# wagband_schematic_pre_route.net
KiCad netlist of a schematic drawn in EAGLE
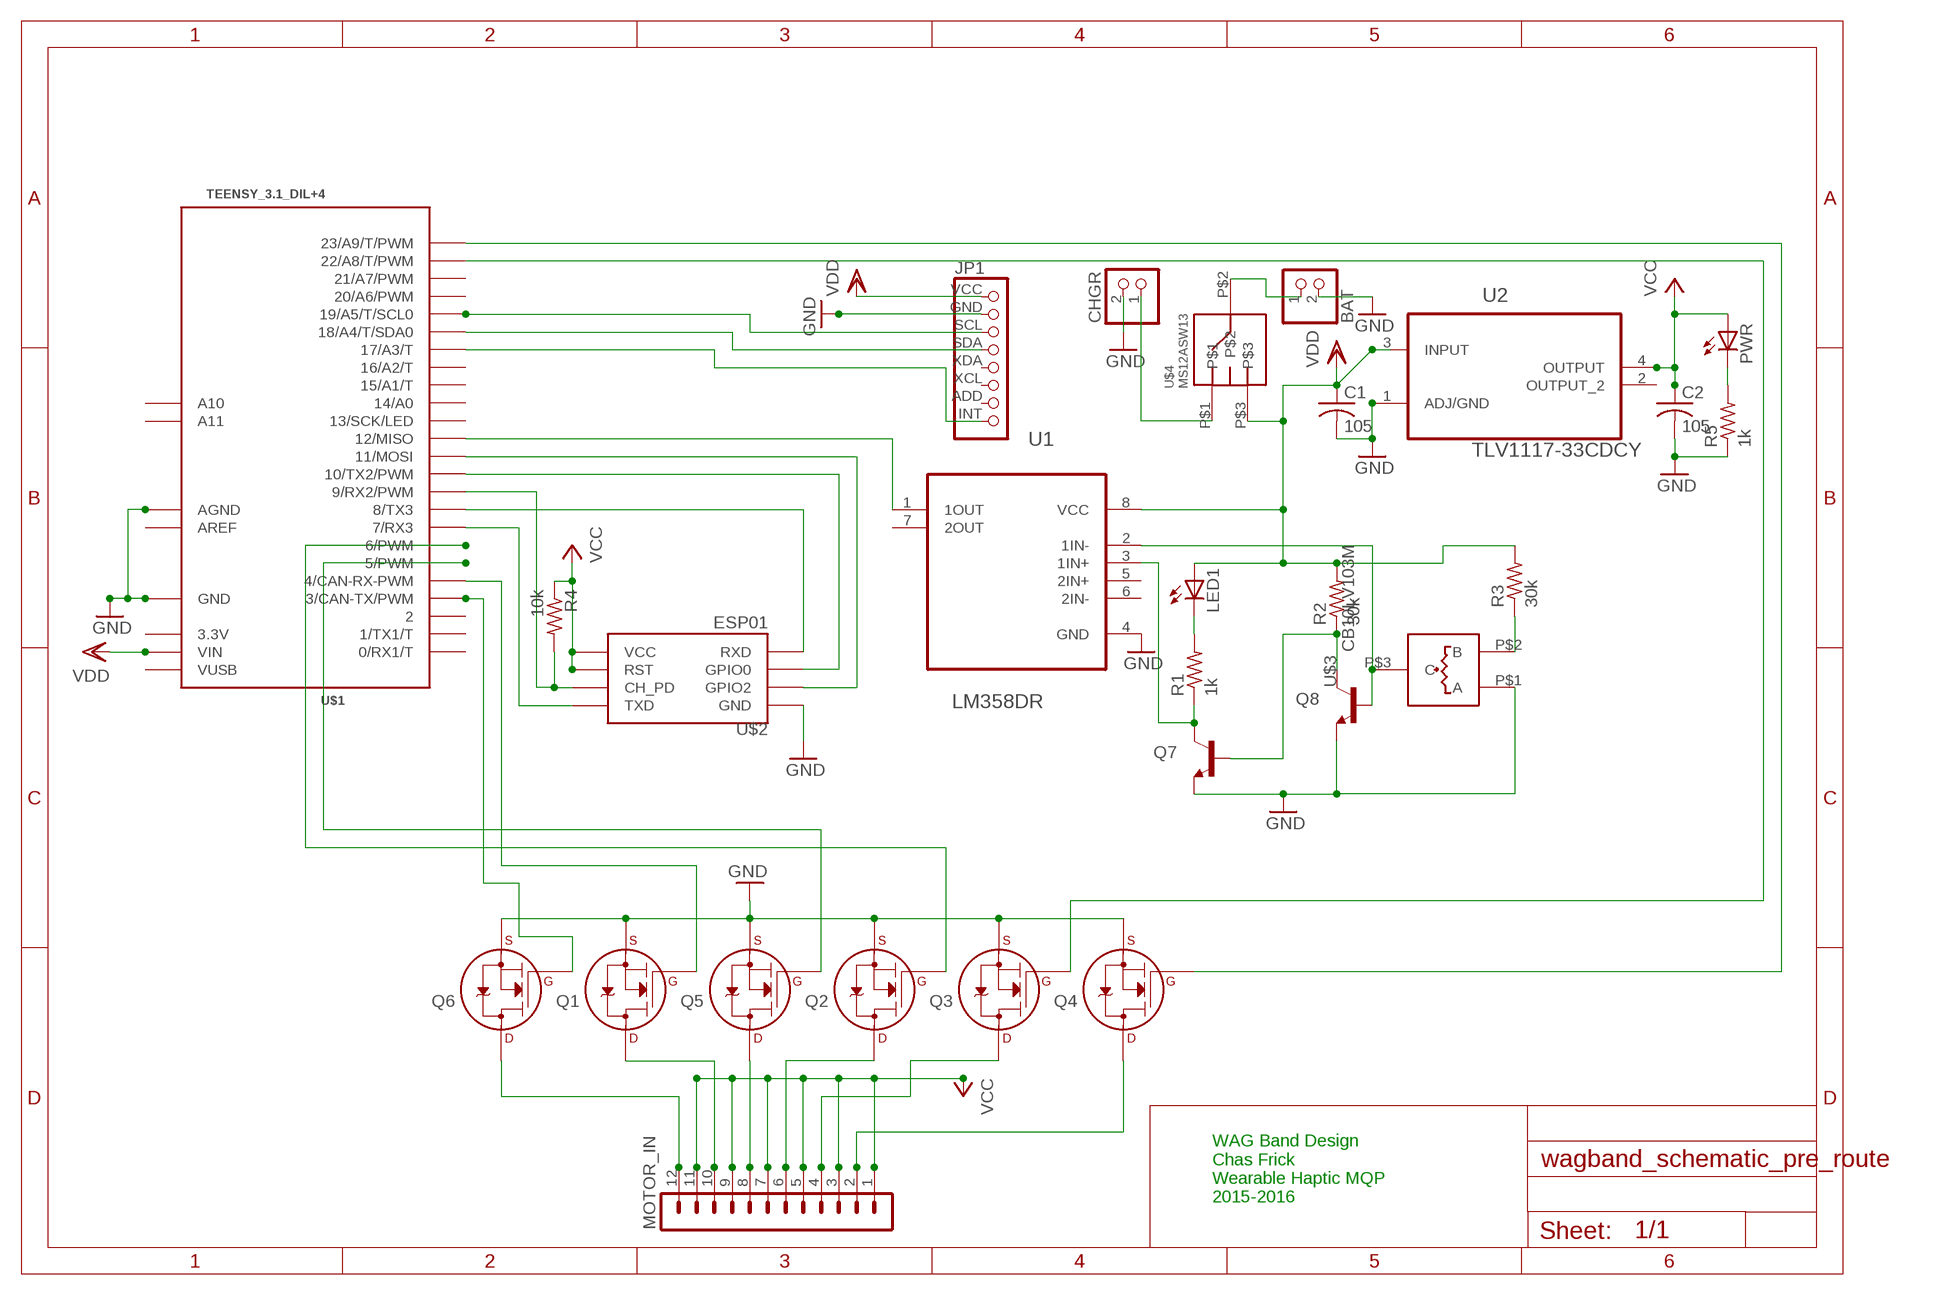
[diagram p0: schematic, sheet 1]

(export (version "E")
  (design (tool "Eeschema 10.0.6"))
  (components
    (comp (ref "BAT")
      (value "JST_2PIN-THM-RA")
      (footprint "eagle-import:JST-PH-2-THM-RA")
      (libsource (lib "eagle-import") (part "JST_2PIN-THM-RA"))
    )
    (comp (ref "C1")
      (value "105")
      (footprint "eagle-import:C0805K")
      (libsource (lib "eagle-import") (part "C-USC0805K"))
    )
    (comp (ref "C2")
      (value "105")
      (footprint "eagle-import:C0805K")
      (libsource (lib "eagle-import") (part "C-USC0805K"))
    )
    (comp (ref "CHGR")
      (value "JST_2PIN-THM-RA")
      (footprint "eagle-import:JST-PH-2-THM-RA")
      (libsource (lib "eagle-import") (part "JST_2PIN-THM-RA"))
    )
    (comp (ref "JP1")
      (value "MPU6050_BREAKOUT")
      (footprint "eagle-import:MPU6050")
      (libsource (lib "eagle-import") (part "MPU6050_BREAKOUT"))
    )
    (comp (ref "LED1")
      (value "LED5MM")
      (footprint "eagle-import:LED5MM")
      (libsource (lib "eagle-import") (part "LED5MM"))
    )
    (comp (ref "MOTOR_IN")
      (value "MA12-1W")
      (footprint "eagle-import:MA12-1W")
      (libsource (lib "eagle-import") (part "MA12-1W"))
    )
    (comp (ref "PWR")
      (value "LED5MM")
      (footprint "eagle-import:LED5MM")
      (libsource (lib "eagle-import") (part "LED5MM"))
    )
    (comp (ref "Q1")
      (value "2N7000_SOT23")
      (footprint "eagle-import:SOT-23")
      (libsource (lib "eagle-import") (part "2N700_SOT230"))
    )
    (comp (ref "Q2")
      (value "2N7000_SOT23")
      (footprint "eagle-import:SOT-23")
      (libsource (lib "eagle-import") (part "2N700_SOT230"))
    )
    (comp (ref "Q3")
      (value "2N7000_SOT23")
      (footprint "eagle-import:SOT-23")
      (libsource (lib "eagle-import") (part "2N700_SOT230"))
    )
    (comp (ref "Q4")
      (value "2N7000_SOT23")
      (footprint "eagle-import:SOT-23")
      (libsource (lib "eagle-import") (part "2N700_SOT230"))
    )
    (comp (ref "Q5")
      (value "2N7000_SOT23")
      (footprint "eagle-import:SOT-23")
      (libsource (lib "eagle-import") (part "2N700_SOT230"))
    )
    (comp (ref "Q6")
      (value "2N7000_SOT23")
      (footprint "eagle-import:SOT-23")
      (libsource (lib "eagle-import") (part "2N700_SOT230"))
    )
    (comp (ref "Q7")
      (value "TRANSISTOR_NPNMMBT3904")
      (footprint "eagle-import:SOT-23")
      (libsource (lib "eagle-import") (part "TRANSISTOR_NPNMMBT3904"))
    )
    (comp (ref "Q8")
      (value "TRANSISTOR_NPNMMBT3904")
      (footprint "eagle-import:SOT-23")
      (libsource (lib "eagle-import") (part "TRANSISTOR_NPNMMBT3904"))
    )
    (comp (ref "R1")
      (value "1k")
      (footprint "eagle-import:R1206")
      (libsource (lib "eagle-import") (part "R-US_R1206"))
    )
    (comp (ref "R2")
      (value "30k")
      (footprint "eagle-import:R1206")
      (libsource (lib "eagle-import") (part "R-US_R1206"))
    )
    (comp (ref "R3")
      (value "30k")
      (footprint "eagle-import:R1206")
      (libsource (lib "eagle-import") (part "R-US_R1206"))
    )
    (comp (ref "R4")
      (value "10k")
      (footprint "eagle-import:R1206")
      (libsource (lib "eagle-import") (part "R-US_R1206"))
    )
    (comp (ref "R5")
      (value "1k")
      (footprint "eagle-import:R1206")
      (libsource (lib "eagle-import") (part "R-US_R1206"))
    )
    (comp (ref "U$1")
      (value "TEENSY_3.1_DIL+4")
      (footprint "eagle-import:TEENSY3-DIL+4")
      (libsource (lib "eagle-import") (part "TEENSY_3.1_DIL+4"))
    )
    (comp (ref "U$2")
      (value "ESP01")
      (footprint "eagle-import:ESP01")
      (libsource (lib "eagle-import") (part "ESP01"))
    )
    (comp (ref "U$3")
      (value "CB10LV103M")
      (footprint "eagle-import:CB10")
      (libsource (lib "eagle-import") (part "CB10LV103M"))
    )
    (comp (ref "U$4")
      (value "MS12ASW13")
      (footprint "eagle-import:SPDT")
      (libsource (lib "eagle-import") (part "MS12ASW13"))
    )
    (comp (ref "U1")
      (value "LM358DR")
      (footprint "eagle-import:SOIC127P600X175-8N")
      (libsource (lib "eagle-import") (part "LM358DR"))
    )
    (comp (ref "U2")
      (value "TLV1117-33CDCY")
      (footprint "eagle-import:SOT230P700X180-4N")
      (libsource (lib "eagle-import") (part "TLV1117-33CDCY"))
    )
  )
  (nets
    (net (code "1") (name "/3.3V") (class "Default")
      (node (ref "U$1") (pin "3.3V") (pinfunction "3.3V_3.3V") (pintype "power_in"))
    )
    (net (code "2") (name "/AREF") (class "Default")
      (node (ref "U$1") (pin "AREF") (pinfunction "AREF_AREF") (pintype "power_in"))
    )
    (net (code "3") (name "/VUSB") (class "Default")
      (node (ref "U$1") (pin "VUSB") (pinfunction "VUSB_VUSB") (pintype "power_in"))
    )
    (net (code "4") (name "GND") (class "Default")
      (node (ref "BAT") (pin "2") (pinfunction "1_2") (pintype "passive"))
      (node (ref "C1") (pin "2") (pinfunction "2_2") (pintype "passive"))
      (node (ref "C2") (pin "2") (pinfunction "2_2") (pintype "passive"))
      (node (ref "CHGR") (pin "2") (pinfunction "1_2") (pintype "passive"))
      (node (ref "JP1") (pin "GND") (pinfunction "GND_GND") (pintype "passive"))
      (node (ref "Q1") (pin "2") (pinfunction "S_2") (pintype "bidirectional"))
      (node (ref "Q2") (pin "2") (pinfunction "S_2") (pintype "bidirectional"))
      (node (ref "Q3") (pin "2") (pinfunction "S_2") (pintype "bidirectional"))
      (node (ref "Q4") (pin "2") (pinfunction "S_2") (pintype "bidirectional"))
      (node (ref "Q5") (pin "2") (pinfunction "S_2") (pintype "bidirectional"))
      (node (ref "Q6") (pin "2") (pinfunction "S_2") (pintype "bidirectional"))
      (node (ref "Q7") (pin "2") (pinfunction "E_2") (pintype "passive"))
      (node (ref "Q8") (pin "2") (pinfunction "E_2") (pintype "passive"))
      (node (ref "R5") (pin "1") (pinfunction "1_1") (pintype "passive"))
      (node (ref "U$1") (pin "AGND") (pinfunction "AGND_AGND") (pintype "power_in"))
      (node (ref "U$1") (pin "GND") (pinfunction "GND_GND") (pintype "power_in"))
      (node (ref "U$2") (pin "GND") (pinfunction "GND_GND") (pintype "bidirectional"))
      (node (ref "U$3") (pin "P$1") (pinfunction "A_P$1") (pintype "bidirectional"))
      (node (ref "U1") (pin "4") (pinfunction "GND_4") (pintype "passive"))
      (node (ref "U2") (pin "1") (pinfunction "ADJ/GND_1") (pintype "input"))
    )
    (net (code "5") (name "Net-(BAT-2)") (class "Default")
      (node (ref "BAT") (pin "1") (pinfunction "2_1") (pintype "passive"))
      (node (ref "U$4") (pin "P$2") (pinfunction "P$2_P$2") (pintype "bidirectional"))
    )
    (net (code "6") (name "Net-(CHGR-2)") (class "Default")
      (node (ref "CHGR") (pin "1") (pinfunction "2_1") (pintype "passive"))
      (node (ref "U$4") (pin "P$1") (pinfunction "P$1_P$1") (pintype "bidirectional"))
    )
    (net (code "7") (name "Net-(LED1-C)") (class "Default")
      (node (ref "LED1") (pin "K") (pinfunction "C_K") (pintype "passive"))
      (node (ref "R1") (pin "2") (pinfunction "2_2") (pintype "passive"))
    )
    (net (code "8") (name "Net-(PWR-C)") (class "Default")
      (node (ref "PWR") (pin "K") (pinfunction "C_K") (pintype "passive"))
      (node (ref "R5") (pin "2") (pinfunction "2_2") (pintype "passive"))
    )
    (net (code "9") (name "Net-(Q1-D)") (class "Default")
      (node (ref "MOTOR_IN") (pin "10") (pinfunction "10_10") (pintype "passive"))
      (node (ref "Q1") (pin "3") (pinfunction "D_3") (pintype "bidirectional"))
    )
    (net (code "10") (name "Net-(Q1-G)") (class "Default")
      (node (ref "Q1") (pin "1") (pinfunction "G_1") (pintype "tri_state"))
      (node (ref "U$1") (pin "4") (pinfunction "4/CAN-RX-PWM_4") (pintype "bidirectional"))
    )
    (net (code "11") (name "Net-(Q2-D)") (class "Default")
      (node (ref "MOTOR_IN") (pin "6") (pinfunction "6_6") (pintype "passive"))
      (node (ref "Q2") (pin "3") (pinfunction "D_3") (pintype "bidirectional"))
    )
    (net (code "12") (name "Net-(Q2-G)") (class "Default")
      (node (ref "Q2") (pin "1") (pinfunction "G_1") (pintype "tri_state"))
      (node (ref "U$1") (pin "6") (pinfunction "6/PWM_6") (pintype "bidirectional"))
    )
    (net (code "13") (name "Net-(Q3-D)") (class "Default")
      (node (ref "MOTOR_IN") (pin "4") (pinfunction "4_4") (pintype "passive"))
      (node (ref "Q3") (pin "3") (pinfunction "D_3") (pintype "bidirectional"))
    )
    (net (code "14") (name "Net-(Q3-G)") (class "Default")
      (node (ref "Q3") (pin "1") (pinfunction "G_1") (pintype "tri_state"))
      (node (ref "U$1") (pin "22/A8") (pinfunction "22/A8/T/PWM_22/A8") (pintype "bidirectional"))
    )
    (net (code "15") (name "Net-(Q4-D)") (class "Default")
      (node (ref "MOTOR_IN") (pin "2") (pinfunction "2_2") (pintype "passive"))
      (node (ref "Q4") (pin "3") (pinfunction "D_3") (pintype "bidirectional"))
    )
    (net (code "16") (name "Net-(Q4-G)") (class "Default")
      (node (ref "Q4") (pin "1") (pinfunction "G_1") (pintype "tri_state"))
      (node (ref "U$1") (pin "23/A9") (pinfunction "23/A9/T/PWM_23/A9") (pintype "bidirectional"))
    )
    (net (code "17") (name "Net-(Q5-D)") (class "Default")
      (node (ref "MOTOR_IN") (pin "8") (pinfunction "8_8") (pintype "passive"))
      (node (ref "Q5") (pin "3") (pinfunction "D_3") (pintype "bidirectional"))
    )
    (net (code "18") (name "Net-(Q5-G)") (class "Default")
      (node (ref "Q5") (pin "1") (pinfunction "G_1") (pintype "tri_state"))
      (node (ref "U$1") (pin "5") (pinfunction "5/PWM_5") (pintype "bidirectional"))
    )
    (net (code "19") (name "Net-(Q6-D)") (class "Default")
      (node (ref "MOTOR_IN") (pin "12") (pinfunction "12_12") (pintype "passive"))
      (node (ref "Q6") (pin "3") (pinfunction "D_3") (pintype "bidirectional"))
    )
    (net (code "20") (name "Net-(Q6-G)") (class "Default")
      (node (ref "Q6") (pin "1") (pinfunction "G_1") (pintype "tri_state"))
      (node (ref "U$1") (pin "3") (pinfunction "3/CAN-TX/PWM_3") (pintype "bidirectional"))
    )
    (net (code "21") (name "Net-(Q7-B)") (class "Default")
      (node (ref "Q7") (pin "1") (pinfunction "B_1") (pintype "passive"))
      (node (ref "Q8") (pin "3") (pinfunction "C_3") (pintype "passive"))
      (node (ref "R2") (pin "1") (pinfunction "1_1") (pintype "passive"))
    )
    (net (code "22") (name "Net-(Q7-C)") (class "Default")
      (node (ref "Q7") (pin "3") (pinfunction "C_3") (pintype "passive"))
      (node (ref "R1") (pin "1") (pinfunction "1_1") (pintype "passive"))
      (node (ref "U1") (pin "3") (pinfunction "1IN+_3") (pintype "input"))
    )
    (net (code "23") (name "Net-(Q8-B)") (class "Default")
      (node (ref "Q8") (pin "1") (pinfunction "B_1") (pintype "passive"))
      (node (ref "U$3") (pin "P$3") (pinfunction "C_P$3") (pintype "bidirectional"))
      (node (ref "U1") (pin "2") (pinfunction "1IN-_2") (pintype "input"))
    )
    (net (code "24") (name "Net-(U$1-7{slash}RX3)") (class "Default")
      (node (ref "U$1") (pin "7") (pinfunction "7/RX3_7") (pintype "bidirectional"))
      (node (ref "U$2") (pin "TX") (pinfunction "TXD_TX") (pintype "bidirectional"))
    )
    (net (code "25") (name "Net-(U$1-8{slash}TX3)") (class "Default")
      (node (ref "U$1") (pin "8") (pinfunction "8/TX3_8") (pintype "bidirectional"))
      (node (ref "U$2") (pin "RX") (pinfunction "RXD_RX") (pintype "bidirectional"))
    )
    (net (code "26") (name "Net-(U$1-9{slash}RX2{slash}PWM)") (class "Default")
      (node (ref "R4") (pin "2") (pinfunction "2_2") (pintype "passive"))
      (node (ref "U$1") (pin "9") (pinfunction "9/RX2/PWM_9") (pintype "bidirectional"))
      (node (ref "U$2") (pin "CH_PD") (pinfunction "CH_PD_CH_PD") (pintype "bidirectional"))
    )
    (net (code "27") (name "Net-(U$1-10{slash}TX2{slash}PWM)") (class "Default")
      (node (ref "U$1") (pin "10") (pinfunction "10/TX2/PWM_10") (pintype "bidirectional"))
      (node (ref "U$2") (pin "GPIO0") (pinfunction "GPIO0_GPIO0") (pintype "bidirectional"))
    )
    (net (code "28") (name "Net-(U$1-11{slash}MOSI)") (class "Default")
      (node (ref "U$1") (pin "11") (pinfunction "11/MOSI_11") (pintype "bidirectional"))
      (node (ref "U$2") (pin "GPIO2") (pinfunction "GPIO2_GPIO2") (pintype "bidirectional"))
    )
    (net (code "29") (name "Net-(U$1-12{slash}MISO)") (class "Default")
      (node (ref "U$1") (pin "12") (pinfunction "12/MISO_12") (pintype "bidirectional"))
      (node (ref "U1") (pin "1") (pinfunction "1OUT_1") (pintype "output"))
    )
    (net (code "30") (name "Net-(U$1-17{slash}A3{slash}T)") (class "Default")
      (node (ref "JP1") (pin "INT") (pinfunction "INT_INT") (pintype "passive"))
      (node (ref "U$1") (pin "17/A3") (pinfunction "17/A3/T_17/A3") (pintype "bidirectional"))
    )
    (net (code "31") (name "Net-(U$1-18{slash}A4{slash}T{slash}SDA0)") (class "Default")
      (node (ref "JP1") (pin "SDA") (pinfunction "SDA_SDA") (pintype "passive"))
      (node (ref "U$1") (pin "18/A4") (pinfunction "18/A4/T/SDA0_18/A4") (pintype "bidirectional"))
    )
    (net (code "32") (name "Net-(U$1-19{slash}A5{slash}T{slash}SCL0)") (class "Default")
      (node (ref "JP1") (pin "SCL") (pinfunction "SCL_SCL") (pintype "passive"))
      (node (ref "U$1") (pin "19/A5") (pinfunction "19/A5/T/SCL0_19/A5") (pintype "bidirectional"))
    )
    (net (code "33") (name "Net-(U$3-B)") (class "Default")
      (node (ref "R3") (pin "1") (pinfunction "1_1") (pintype "passive"))
      (node (ref "U$3") (pin "P$2") (pinfunction "B_P$2") (pintype "bidirectional"))
    )
    (net (code "34") (name "VCC") (class "Default")
      (node (ref "C2") (pin "1") (pinfunction "1_1") (pintype "passive"))
      (node (ref "MOTOR_IN") (pin "1") (pinfunction "1_1") (pintype "passive"))
      (node (ref "MOTOR_IN") (pin "11") (pinfunction "11_11") (pintype "passive"))
      (node (ref "MOTOR_IN") (pin "3") (pinfunction "3_3") (pintype "passive"))
      (node (ref "MOTOR_IN") (pin "5") (pinfunction "5_5") (pintype "passive"))
      (node (ref "MOTOR_IN") (pin "7") (pinfunction "7_7") (pintype "passive"))
      (node (ref "MOTOR_IN") (pin "9") (pinfunction "9_9") (pintype "passive"))
      (node (ref "PWR") (pin "A") (pinfunction "A_A") (pintype "passive"))
      (node (ref "R4") (pin "1") (pinfunction "1_1") (pintype "passive"))
      (node (ref "U$2") (pin "RST") (pinfunction "RST_RST") (pintype "bidirectional"))
      (node (ref "U$2") (pin "VCC") (pinfunction "VCC_VCC") (pintype "bidirectional"))
      (node (ref "U2") (pin "4") (pinfunction "OUTPUT_4") (pintype "output"))
    )
    (net (code "35") (name "VDD") (class "Default")
      (node (ref "C1") (pin "1") (pinfunction "1_1") (pintype "passive"))
      (node (ref "JP1") (pin "VCC") (pinfunction "VCC_VCC") (pintype "passive"))
      (node (ref "LED1") (pin "A") (pinfunction "A_A") (pintype "passive"))
      (node (ref "R2") (pin "2") (pinfunction "2_2") (pintype "passive"))
      (node (ref "R3") (pin "2") (pinfunction "2_2") (pintype "passive"))
      (node (ref "U$1") (pin "VIN") (pinfunction "VIN_VIN") (pintype "power_in"))
      (node (ref "U$4") (pin "P$3") (pinfunction "P$3_P$3") (pintype "bidirectional"))
      (node (ref "U1") (pin "8") (pinfunction "VCC_8") (pintype "power_in"))
      (node (ref "U2") (pin "3") (pinfunction "INPUT_3") (pintype "input"))
    )
    (net (code "36") (name "unconnected-(JP1-PadADD)") (class "Default")
      (node (ref "JP1") (pin "ADD") (pinfunction "ADD_ADD") (pintype "passive"))
    )
    (net (code "37") (name "unconnected-(JP1-PadXCL)") (class "Default")
      (node (ref "JP1") (pin "XCL") (pinfunction "XCL_XCL") (pintype "passive"))
    )
    (net (code "38") (name "unconnected-(JP1-PadXDA)") (class "Default")
      (node (ref "JP1") (pin "XDA") (pinfunction "XDA_XDA") (pintype "passive"))
    )
    (net (code "39") (name "unconnected-(U$1-0{slash}RX1{slash}T-Pad0)") (class "Default")
      (node (ref "U$1") (pin "0") (pinfunction "0/RX1/T_0") (pintype "bidirectional"))
    )
    (net (code "40") (name "unconnected-(U$1-1{slash}TX1{slash}T-Pad1)") (class "Default")
      (node (ref "U$1") (pin "1") (pinfunction "1/TX1/T_1") (pintype "bidirectional"))
    )
    (net (code "41") (name "unconnected-(U$1-13{slash}SCK{slash}LED-Pad13)") (class "Default")
      (node (ref "U$1") (pin "13") (pinfunction "13/SCK/LED_13") (pintype "bidirectional"))
    )
    (net (code "42") (name "unconnected-(U$1-15{slash}A1{slash}T-Pad15{slash}A1)") (class "Default")
      (node (ref "U$1") (pin "15/A1") (pinfunction "15/A1/T_15/A1") (pintype "bidirectional"))
    )
    (net (code "43") (name "unconnected-(U$1-16{slash}A2{slash}T-Pad16{slash}A2)") (class "Default")
      (node (ref "U$1") (pin "16/A2") (pinfunction "16/A2/T_16/A2") (pintype "bidirectional"))
    )
    (net (code "44") (name "unconnected-(U$1-20{slash}A6{slash}PWM-Pad20{slash}A6)") (class "Default")
      (node (ref "U$1") (pin "20/A6") (pinfunction "20/A6/PWM_20/A6") (pintype "bidirectional"))
    )
    (net (code "45") (name "unconnected-(U$1-21{slash}A7{slash}PWM-Pad21{slash}A7)") (class "Default")
      (node (ref "U$1") (pin "21/A7") (pinfunction "21/A7/PWM_21/A7") (pintype "bidirectional"))
    )
    (net (code "46") (name "unconnected-(U$1-Pad2)") (class "Default")
      (node (ref "U$1") (pin "2") (pinfunction "2_2") (pintype "bidirectional"))
    )
    (net (code "47") (name "unconnected-(U$1-Pad14{slash}A0)") (class "Default")
      (node (ref "U$1") (pin "14/A0") (pinfunction "14/A0_14/A0") (pintype "bidirectional"))
    )
    (net (code "48") (name "unconnected-(U$1-PadA10)") (class "Default")
      (node (ref "U$1") (pin "A10") (pinfunction "A10_A10") (pintype "bidirectional"))
    )
    (net (code "49") (name "unconnected-(U$1-PadA11)") (class "Default")
      (node (ref "U$1") (pin "A11") (pinfunction "A11_A11") (pintype "bidirectional"))
    )
    (net (code "50") (name "unconnected-(U1-2IN+-Pad5)") (class "Default")
      (node (ref "U1") (pin "5") (pinfunction "2IN+_5") (pintype "input"))
    )
    (net (code "51") (name "unconnected-(U1-2IN--Pad6)") (class "Default")
      (node (ref "U1") (pin "6") (pinfunction "2IN-_6") (pintype "input"))
    )
    (net (code "52") (name "unconnected-(U1-2OUT-Pad7)") (class "Default")
      (node (ref "U1") (pin "7") (pinfunction "2OUT_7") (pintype "output"))
    )
    (net (code "53") (name "unconnected-(U2-OUTPUT_2-Pad2)") (class "Default")
      (node (ref "U2") (pin "2") (pinfunction "OUTPUT_2_2") (pintype "output"))
    )
  )
)
